# mcu.net
KiCad netlist of a schematic drawn in Altium Designer
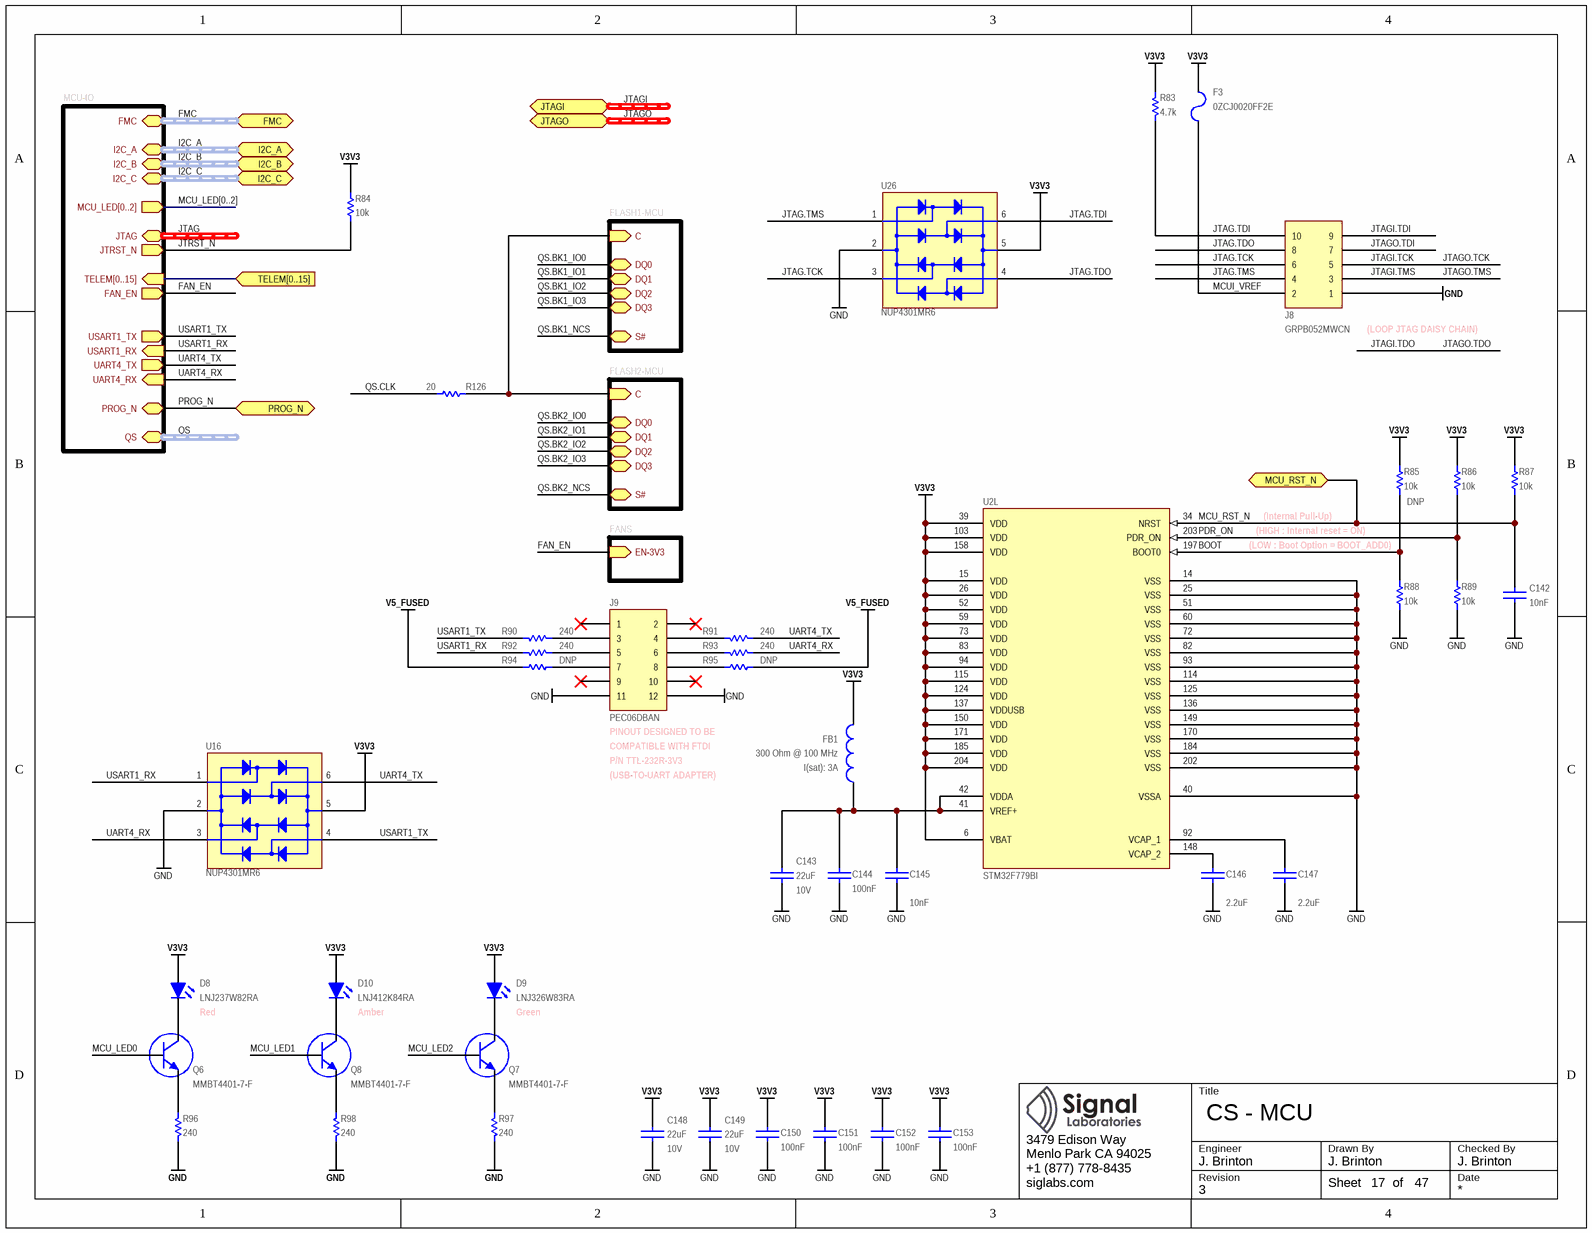
[diagram p0: mcu.SchDoc]

(export (version "E")
  (design (tool "Eeschema 10.0.6"))
  (components
    (comp (ref "C142")
      (value "10nF")
      (footprint "CAPC100X50X55L25N")
      (description "Ceramic Capacitor 10nF ±10% 50V X7R 0402")
      (fields (field (name "TOLERANCE") "±10%") (field (name "MANUFACTURER") "Murata"))
      (libsource (lib "generic") (part "Cap"))
    )
    (comp (ref "C143")
      (value "22uF")
      (footprint "CAPC200X125X145L45N")
      (description "Ceramic Capacitor 22uF ±20% 10V X7S 0805")
      (fields
        (field (name "MANUFACTURER") "TDK")
        (field (name "TOLERANCE") "±20%")
        (field (name "VOLTAGE") "10V")
      )
      (libsource (lib "") (part "CAP_1"))
    )
    (comp (ref "C144")
      (value "100nF")
      (footprint "CAPC100X50X55L25N")
      (description "Ceramic Capacitor 100nF ±10% 50V X7R 0402")
      (fields (field (name "VOLTAGE") "50V") (field (name "MANUFACTURER") "Murata"))
      (libsource (lib "generic") (part "CAP"))
    )
    (comp (ref "C145")
      (value "10nF")
      (footprint "CAPC100X50X55L25N")
      (description "Ceramic Capacitor 10nF ±10% 50V X7R 0402")
      (fields (field (name "TOLERANCE") "±10%") (field (name "MANUFACTURER") "Murata"))
      (libsource (lib "generic") (part "Cap"))
    )
    (comp (ref "C146")
      (value "2.2uF")
      (footprint "CAPC160X80X90L20N")
      (description "Ceramic Capacitor 2.2uF ±20% 10V X7R 0603")
      (fields (field (name "TOLERANCE") "±20%") (field (name "MANUFACTURER") "TDK"))
      (libsource (lib "generic") (part "Cap"))
    )
    (comp (ref "C147")
      (value "2.2uF")
      (footprint "CAPC160X80X90L20N")
      (description "Ceramic Capacitor 2.2uF ±20% 10V X7R 0603")
      (fields (field (name "TOLERANCE") "±20%") (field (name "MANUFACTURER") "TDK"))
      (libsource (lib "generic") (part "Cap"))
    )
    (comp (ref "C148")
      (value "22uF")
      (footprint "CAPC200X125X145L45N")
      (description "Ceramic Capacitor 22uF ±20% 10V X7S 0805")
      (fields
        (field (name "MANUFACTURER") "TDK")
        (field (name "TOLERANCE") "±20%")
        (field (name "VOLTAGE") "10V")
      )
      (libsource (lib "") (part "CAP_1"))
    )
    (comp (ref "C149")
      (value "22uF")
      (footprint "CAPC200X125X145L45N")
      (description "Ceramic Capacitor 22uF ±20% 10V X7S 0805")
      (fields
        (field (name "MANUFACTURER") "TDK")
        (field (name "TOLERANCE") "±20%")
        (field (name "VOLTAGE") "10V")
      )
      (libsource (lib "") (part "CAP_1"))
    )
    (comp (ref "C150")
      (value "100nF")
      (footprint "CAPC100X50X55L25N")
      (description "Ceramic Capacitor 100nF ±10% 50V X7R 0402")
      (fields (field (name "VOLTAGE") "50V") (field (name "MANUFACTURER") "Murata"))
      (libsource (lib "generic") (part "CAP"))
    )
    (comp (ref "C151")
      (value "100nF")
      (footprint "CAPC100X50X55L25N")
      (description "Ceramic Capacitor 100nF ±10% 50V X7R 0402")
      (fields (field (name "VOLTAGE") "50V") (field (name "MANUFACTURER") "Murata"))
      (libsource (lib "generic") (part "CAP"))
    )
    (comp (ref "C152")
      (value "100nF")
      (footprint "CAPC100X50X55L25N")
      (description "Ceramic Capacitor 100nF ±10% 50V X7R 0402")
      (fields (field (name "VOLTAGE") "50V") (field (name "MANUFACTURER") "Murata"))
      (libsource (lib "generic") (part "CAP"))
    )
    (comp (ref "C153")
      (value "100nF")
      (footprint "CAPC100X50X55L25N")
      (description "Ceramic Capacitor 100nF ±10% 50V X7R 0402")
      (fields (field (name "VOLTAGE") "50V") (field (name "MANUFACTURER") "Murata"))
      (libsource (lib "generic") (part "CAP"))
    )
    (comp (ref "D8")
      (value "LNJ237W82RA")
      (footprint "0603_LED")
      (description "LED, SMT 0603, Color Red, 5mA, 1.85V")
      (fields (field (name "MANUFACTURER") "Panasonic"))
      (libsource (lib "generic") (part "LED0603RD"))
    )
    (comp (ref "D9")
      (value "LNJ326W83RA")
      (footprint "0603_LED")
      (description "LED, SMT 0603, Color Green, 10mA, 2.05V")
      (fields (field (name "MANUFACTURER") "Panasonic"))
      (libsource (lib "generic") (part "LED0603GR"))
    )
    (comp (ref "D10")
      (value "LNJ412K84RA")
      (footprint "0603_LED")
      (description "LED, SMT 0603, Color Amber, 10mA, 2.05V")
      (fields (field (name "MANUFACTURER") "Panasonic"))
      (libsource (lib "generic") (part "LED0603Y"))
    )
    (comp (ref "F3")
      (value "0ZCJ0020FF2E")
      (footprint "generic:1206")
      (description "PTC Resettable Fuse, 0.2A, 30V, SMD 1206")
      (fields (field (name "MANUFACTURER") "Bell Fuse"))
      (libsource (lib "bel-fuse") (part "0ZCJ0020FF2E"))
    )
    (comp (ref "FB1")
      (value "300 Ohm @ 100 MHz")
      (footprint "0805")
      (description "Ferrite Chip 300 Ohm @ 100MHz; 3A")
      (fields
        (field (name "MANUFACTURER") "Wurth Electronics, Inc")
        (field (name "I(SAT)") "3A")
        (field (name "Comment") "742792031")
      )
      (libsource (lib "generic") (part "INDUCTOR"))
    )
    (comp (ref "J8")
      (value "GRPB052MWCN")
      (footprint "sullins:GRPB052MWCN")
      (description "Male Header, 0.050\" Pitch, 2x5 Position, Right Angle")
      (fields (field (name "MANUFACTURER") "Sullins"))
      (libsource (lib "sullins") (part "GRPB052VWVN"))
    )
    (comp (ref "J9")
      (value "PEC06DBAN")
      (footprint "HDR2X6H")
      (description "Header, 6-Pin, Dual row, Right Angle")
      (fields (field (name "MANUFACTURER") "Sullins"))
      (libsource (lib "Miscellaneous Connectors") (part "Header 6X2H"))
    )
    (comp (ref "Q6")
      (value "MMBT4401-7-F")
      (footprint "generic:SOT23")
      (description "NPN Small Signal Transistor SMD SOT-23")
      (fields (field (name "MANUFACTURER P/N") "MMBT4401-7-F") (field (name "MANUFACTURER") "Diodes, Inc."))
      (libsource (lib "diodes_inc") (part "MMBT4401-7-F"))
    )
    (comp (ref "Q7")
      (value "MMBT4401-7-F")
      (footprint "generic:SOT23")
      (description "NPN Small Signal Transistor SMD SOT-23")
      (fields (field (name "MANUFACTURER P/N") "MMBT4401-7-F") (field (name "MANUFACTURER") "Diodes, Inc."))
      (libsource (lib "diodes_inc") (part "MMBT4401-7-F"))
    )
    (comp (ref "Q8")
      (value "MMBT4401-7-F")
      (footprint "generic:SOT23")
      (description "NPN Small Signal Transistor SMD SOT-23")
      (fields (field (name "MANUFACTURER P/N") "MMBT4401-7-F") (field (name "MANUFACTURER") "Diodes, Inc."))
      (libsource (lib "diodes_inc") (part "MMBT4401-7-F"))
    )
    (comp (ref "R83")
      (value "4.7k")
      (footprint "RESC1005X40N")
      (description "Thick Film Resistor 4.7k ±1% 0.1W 75V 0402")
      (fields (field (name "TOLERANCE") "±1%") (field (name "MANUFACTURER") "Panasonic"))
      (libsource (lib "generic") (part "RES"))
    )
    (comp (ref "R84")
      (value "10k")
      (footprint "RESC1005X40N")
      (description "Thick Film Resistor 10k ±1% 0.1W 50V 0402")
      (fields (field (name "MANUFACTURER") "Panasonic") (field (name "TOLERANCE") "±1%"))
      (libsource (lib "generic") (part "RES"))
    )
    (comp (ref "R85")
      (value "10k")
      (footprint "RESC1005X40N")
      (description "Thick Film Resistor 10k ±1% 0.1W 50V 0402")
      (fields
        (field (name "MANUFACTURER") "Panasonic")
        (field (name "TOLERANCE") "±1%")
        (field (name "DO NOT PLACE") "DNP")
      )
      (libsource (lib "generic") (part "RES"))
    )
    (comp (ref "R86")
      (value "10k")
      (footprint "RESC1005X40N")
      (description "Thick Film Resistor 10k ±1% 0.1W 50V 0402")
      (fields (field (name "MANUFACTURER") "Panasonic") (field (name "TOLERANCE") "±1%"))
      (libsource (lib "generic") (part "RES"))
    )
    (comp (ref "R87")
      (value "10k")
      (footprint "RESC1005X40N")
      (description "Thick Film Resistor 10k ±1% 0.1W 50V 0402")
      (fields (field (name "MANUFACTURER") "Panasonic") (field (name "TOLERANCE") "±1%"))
      (libsource (lib "generic") (part "RES"))
    )
    (comp (ref "R88")
      (value "10k")
      (footprint "RESC1005X40N")
      (description "Thick Film Resistor 10k ±1% 0.1W 50V 0402")
      (fields (field (name "MANUFACTURER") "Panasonic") (field (name "TOLERANCE") "±1%"))
      (libsource (lib "generic") (part "RES"))
    )
    (comp (ref "R89")
      (value "10k")
      (footprint "RESC1005X40N")
      (description "Thick Film Resistor 10k ±1% 0.1W 50V 0402")
      (fields (field (name "MANUFACTURER") "Panasonic") (field (name "TOLERANCE") "±1%"))
      (libsource (lib "generic") (part "RES"))
    )
    (comp (ref "R90")
      (value "240")
      (footprint "RESC1005X40N")
      (description "Thick Film Resistor 240 ±1% 0.1W 75V 0402")
      (fields (field (name "TOLERANCE") "±1%") (field (name "MANUFACTURER") "Panasonic"))
      (libsource (lib "generic") (part "RES"))
    )
    (comp (ref "R91")
      (value "240")
      (footprint "RESC1005X40N")
      (description "Thick Film Resistor 240 ±1% 0.1W 75V 0402")
      (fields (field (name "TOLERANCE") "±1%") (field (name "MANUFACTURER") "Panasonic"))
      (libsource (lib "generic") (part "RES"))
    )
    (comp (ref "R92")
      (value "240")
      (footprint "RESC1005X40N")
      (description "Thick Film Resistor 240 ±1% 0.1W 75V 0402")
      (fields (field (name "TOLERANCE") "±1%") (field (name "MANUFACTURER") "Panasonic"))
      (libsource (lib "generic") (part "RES"))
    )
    (comp (ref "R93")
      (value "240")
      (footprint "RESC1005X40N")
      (description "Thick Film Resistor 240 ±1% 0.1W 75V 0402")
      (fields (field (name "TOLERANCE") "±1%") (field (name "MANUFACTURER") "Panasonic"))
      (libsource (lib "generic") (part "RES"))
    )
    (comp (ref "R94")
      (value "SOLDER_LINK")
      (footprint "SOLDERLINK0603X26N")
      (description "Solder Link")
      (fields (field (name "DO NOT PLACE") "DNP"))
      (libsource (lib "generic") (part "RES"))
    )
    (comp (ref "R95")
      (value "SOLDER_LINK")
      (footprint "SOLDERLINK0603X26N")
      (description "Solder Link")
      (fields (field (name "DO NOT PLACE") "DNP"))
      (libsource (lib "generic") (part "RES"))
    )
    (comp (ref "R96")
      (value "240")
      (footprint "RESC1005X40N")
      (description "Thick Film Resistor 240 ±1% 0.1W 75V 0402")
      (fields (field (name "TOLERANCE") "±1%") (field (name "MANUFACTURER") "Panasonic"))
      (libsource (lib "generic") (part "RES"))
    )
    (comp (ref "R97")
      (value "240")
      (footprint "RESC1005X40N")
      (description "Thick Film Resistor 240 ±1% 0.1W 75V 0402")
      (fields (field (name "TOLERANCE") "±1%") (field (name "MANUFACTURER") "Panasonic"))
      (libsource (lib "generic") (part "RES"))
    )
    (comp (ref "R98")
      (value "240")
      (footprint "RESC1005X40N")
      (description "Thick Film Resistor 240 ±1% 0.1W 75V 0402")
      (fields (field (name "TOLERANCE") "±1%") (field (name "MANUFACTURER") "Panasonic"))
      (libsource (lib "generic") (part "RES"))
    )
    (comp (ref "R126")
      (value "20")
      (footprint "RESC1005X40N")
      (description "Thick Film Resistor 20 ±1% 0.1W 75V 0402")
      (fields (field (name "TOLERANCE") "±1%") (field (name "MANUFACTURER") "Panasonic"))
      (libsource (lib "generic") (part "RES"))
    )
    (comp (ref "U2")
      (value "STM32F779BI")
      (footprint "LQFP208")
      (description "STM32 Microcontroller")
      (fields (field (name "MANUFACTURER") "ST Microelectronics"))
      (libsource (lib "hadley") (part "STM32F746BGT6"))
    )
    (comp (ref "U16")
      (value "NUP4301MR6")
      (footprint "generic:SOT23-6")
      (description "4-Lane TVS Diode Array")
      (fields (field (name "MANUFACTURER") "On Semiconductor"))
      (libsource (lib "on_semi") (part "NUP4301MR6"))
    )
    (comp (ref "U26")
      (value "NUP4301MR6")
      (footprint "generic:SOT23-6")
      (description "4-Lane TVS Diode Array")
      (fields (field (name "MANUFACTURER") "On Semiconductor"))
      (libsource (lib "on_semi") (part "NUP4301MR6"))
    )
  )
  (nets
    (net (code "25") (name "/BOOT") (class "Default")
      (node (ref "R85") (pin "1") (pinfunction "1_1") (pintype "passive"))
      (node (ref "R88") (pin "2") (pinfunction "2_2") (pintype "passive"))
      (node (ref "U2") (pin "197") (pinfunction "BOOT0_197") (pintype "input"))
    )
    (net (code "26") (name "/C") (class "Default")
      (node (ref "R126") (pin "2") (pinfunction "2_2") (pintype "passive"))
    )
    (net (code "28") (name "/JTAG.TCK") (class "Default")
      (node (ref "J8") (pin "6") (pinfunction "6_6") (pintype "passive"))
      (node (ref "U26") (pin "3") (pinfunction "B_3") (pintype "passive"))
    )
    (net (code "29") (name "/JTAG.TDI") (class "Default")
      (node (ref "J8") (pin "10") (pinfunction "10_10") (pintype "passive"))
      (node (ref "R83") (pin "1") (pinfunction "1_1") (pintype "passive"))
      (node (ref "U26") (pin "6") (pinfunction "D_6") (pintype "passive"))
    )
    (net (code "30") (name "/JTAG.TDO") (class "Default")
      (node (ref "J8") (pin "8") (pinfunction "8_8") (pintype "passive"))
      (node (ref "U26") (pin "4") (pinfunction "C_4") (pintype "passive"))
    )
    (net (code "31") (name "/JTAG.TMS") (class "Default")
      (node (ref "J8") (pin "4") (pinfunction "4_4") (pintype "passive"))
      (node (ref "U26") (pin "1") (pinfunction "A_1") (pintype "passive"))
    )
    (net (code "32") (name "/JTAGI.TCK") (class "Default")
      (node (ref "J8") (pin "5") (pinfunction "5_5") (pintype "passive"))
    )
    (net (code "33") (name "/JTAGI.TDI") (class "Default")
      (node (ref "J8") (pin "9") (pinfunction "9_9") (pintype "passive"))
    )
    (net (code "35") (name "/JTAGI.TMS") (class "Default")
      (node (ref "J8") (pin "3") (pinfunction "3_3") (pintype "passive"))
    )
    (net (code "36") (name "/JTAGO.TDI") (class "Default")
      (node (ref "J8") (pin "7") (pinfunction "7_7") (pintype "passive"))
    )
    (net (code "37") (name "/JTRST_N") (class "Default")
      (node (ref "R84") (pin "1") (pinfunction "1_1") (pintype "passive"))
    )
    (net (code "38") (name "/MCUI_VREF") (class "Default")
      (node (ref "F3") (pin "2") (pinfunction "2_2") (pintype "passive"))
      (node (ref "J8") (pin "2") (pinfunction "2_2") (pintype "passive"))
    )
    (net (code "39") (name "/MCU_LED0") (class "Default")
      (node (ref "Q6") (pin "1") (pinfunction "B_1") (pintype "passive"))
    )
    (net (code "40") (name "/MCU_LED1") (class "Default")
      (node (ref "Q8") (pin "1") (pinfunction "B_1") (pintype "passive"))
    )
    (net (code "41") (name "/MCU_LED2") (class "Default")
      (node (ref "Q7") (pin "1") (pinfunction "B_1") (pintype "passive"))
    )
    (net (code "43") (name "/MCU_RST_N") (class "Default")
      (node (ref "C142") (pin "2") (pinfunction "2_2") (pintype "passive"))
      (node (ref "R87") (pin "1") (pinfunction "1_1") (pintype "passive"))
      (node (ref "U2") (pin "34") (pinfunction "NRST_34") (pintype "input"))
    )
    (net (code "44") (name "/PDR_ON") (class "Default")
      (node (ref "R86") (pin "1") (pinfunction "1_1") (pintype "passive"))
      (node (ref "R89") (pin "2") (pinfunction "2_2") (pintype "passive"))
      (node (ref "U2") (pin "203") (pinfunction "PDR_ON_203") (pintype "input"))
    )
    (net (code "56") (name "/QS.CLK") (class "Default")
      (node (ref "R126") (pin "1") (pinfunction "1_1") (pintype "passive"))
    )
    (net (code "58") (name "/UART4_RX") (class "Default")
      (node (ref "R93") (pin "2") (pinfunction "2_2") (pintype "passive"))
      (node (ref "U16") (pin "3") (pinfunction "B_3") (pintype "passive"))
    )
    (net (code "59") (name "/UART4_TX") (class "Default")
      (node (ref "R91") (pin "2") (pinfunction "2_2") (pintype "passive"))
      (node (ref "U16") (pin "6") (pinfunction "D_6") (pintype "passive"))
    )
    (net (code "60") (name "/USART1_RX") (class "Default")
      (node (ref "R92") (pin "1") (pinfunction "1_1") (pintype "passive"))
      (node (ref "U16") (pin "1") (pinfunction "A_1") (pintype "passive"))
    )
    (net (code "61") (name "/USART1_TX") (class "Default")
      (node (ref "R90") (pin "1") (pinfunction "1_1") (pintype "passive"))
      (node (ref "U16") (pin "4") (pinfunction "C_4") (pintype "passive"))
    )
    (net (code "70") (name "GND") (class "Default")
      (node (ref "C142") (pin "1") (pinfunction "1_1") (pintype "passive"))
      (node (ref "C143") (pin "2") (pinfunction "2_2") (pintype "passive"))
      (node (ref "C144") (pin "1") (pinfunction "1_1") (pintype "passive"))
      (node (ref "C145") (pin "1") (pinfunction "1_1") (pintype "passive"))
      (node (ref "C146") (pin "1") (pinfunction "1_1") (pintype "passive"))
      (node (ref "C147") (pin "1") (pinfunction "1_1") (pintype "passive"))
      (node (ref "C148") (pin "2") (pinfunction "2_2") (pintype "passive"))
      (node (ref "C149") (pin "2") (pinfunction "2_2") (pintype "passive"))
      (node (ref "C150") (pin "1") (pinfunction "1_1") (pintype "passive"))
      (node (ref "C151") (pin "1") (pinfunction "1_1") (pintype "passive"))
      (node (ref "C152") (pin "1") (pinfunction "1_1") (pintype "passive"))
      (node (ref "C153") (pin "1") (pinfunction "1_1") (pintype "passive"))
      (node (ref "J8") (pin "1") (pinfunction "1_1") (pintype "passive"))
      (node (ref "J9") (pin "11") (pinfunction "11_11") (pintype "passive"))
      (node (ref "J9") (pin "12") (pinfunction "12_12") (pintype "passive"))
      (node (ref "R88") (pin "1") (pinfunction "1_1") (pintype "passive"))
      (node (ref "R89") (pin "1") (pinfunction "1_1") (pintype "passive"))
      (node (ref "R96") (pin "2") (pinfunction "2_2") (pintype "passive"))
      (node (ref "R97") (pin "2") (pinfunction "2_2") (pintype "passive"))
      (node (ref "R98") (pin "2") (pinfunction "2_2") (pintype "passive"))
      (node (ref "U16") (pin "2") (pinfunction "VN_2") (pintype "passive"))
      (node (ref "U2") (pin "114") (pinfunction "VSS_114") (pintype "power_in"))
      (node (ref "U2") (pin "125") (pinfunction "VSS_125") (pintype "power_in"))
      (node (ref "U2") (pin "136") (pinfunction "VSS_136") (pintype "power_in"))
      (node (ref "U2") (pin "14") (pinfunction "VSS_14") (pintype "power_in"))
      (node (ref "U2") (pin "149") (pinfunction "VSS_149") (pintype "power_in"))
      (node (ref "U2") (pin "170") (pinfunction "VSS_170") (pintype "power_in"))
      (node (ref "U2") (pin "184") (pinfunction "VSS_184") (pintype "power_in"))
      (node (ref "U2") (pin "202") (pinfunction "VSS_202") (pintype "power_in"))
      (node (ref "U2") (pin "25") (pinfunction "VSS_25") (pintype "power_in"))
      (node (ref "U2") (pin "40") (pinfunction "VSSA_40") (pintype "power_in"))
      (node (ref "U2") (pin "51") (pinfunction "VSS_51") (pintype "power_in"))
      (node (ref "U2") (pin "60") (pinfunction "VSS_60") (pintype "power_in"))
      (node (ref "U2") (pin "72") (pinfunction "VSS_72") (pintype "power_in"))
      (node (ref "U2") (pin "82") (pinfunction "VSS_82") (pintype "power_in"))
      (node (ref "U2") (pin "93") (pinfunction "VSS_93") (pintype "power_in"))
      (node (ref "U26") (pin "2") (pinfunction "VN_2") (pintype "passive"))
    )
    (net (code "71") (name "Net-(D8-K)") (class "Default")
      (node (ref "D8") (pin "2") (pinfunction "K_2") (pintype "passive"))
      (node (ref "Q6") (pin "3") (pinfunction "C_3") (pintype "passive"))
    )
    (net (code "72") (name "Net-(D9-K)") (class "Default")
      (node (ref "D9") (pin "2") (pinfunction "K_2") (pintype "passive"))
      (node (ref "Q7") (pin "3") (pinfunction "C_3") (pintype "passive"))
    )
    (net (code "73") (name "Net-(D10-K)") (class "Default")
      (node (ref "D10") (pin "2") (pinfunction "K_2") (pintype "passive"))
      (node (ref "Q8") (pin "3") (pinfunction "C_3") (pintype "passive"))
    )
    (net (code "74") (name "Net-(J9-Pad3)") (class "Default")
      (node (ref "J9") (pin "3") (pinfunction "3_3") (pintype "passive"))
      (node (ref "R90") (pin "2") (pinfunction "2_2") (pintype "passive"))
    )
    (net (code "75") (name "Net-(J9-Pad4)") (class "Default")
      (node (ref "J9") (pin "4") (pinfunction "4_4") (pintype "passive"))
      (node (ref "R91") (pin "1") (pinfunction "1_1") (pintype "passive"))
    )
    (net (code "76") (name "Net-(J9-Pad5)") (class "Default")
      (node (ref "J9") (pin "5") (pinfunction "5_5") (pintype "passive"))
      (node (ref "R92") (pin "2") (pinfunction "2_2") (pintype "passive"))
    )
    (net (code "77") (name "Net-(J9-Pad6)") (class "Default")
      (node (ref "J9") (pin "6") (pinfunction "6_6") (pintype "passive"))
      (node (ref "R93") (pin "1") (pinfunction "1_1") (pintype "passive"))
    )
    (net (code "78") (name "Net-(J9-Pad7)") (class "Default")
      (node (ref "J9") (pin "7") (pinfunction "7_7") (pintype "passive"))
      (node (ref "R94") (pin "1") (pinfunction "1_1") (pintype "passive"))
    )
    (net (code "79") (name "Net-(J9-Pad8)") (class "Default")
      (node (ref "J9") (pin "8") (pinfunction "8_8") (pintype "passive"))
      (node (ref "R95") (pin "2") (pinfunction "2_2") (pintype "passive"))
    )
    (net (code "80") (name "Net-(Q6-E)") (class "Default")
      (node (ref "Q6") (pin "2") (pinfunction "E_2") (pintype "passive"))
      (node (ref "R96") (pin "1") (pinfunction "1_1") (pintype "passive"))
    )
    (net (code "81") (name "Net-(Q7-E)") (class "Default")
      (node (ref "Q7") (pin "2") (pinfunction "E_2") (pintype "passive"))
      (node (ref "R97") (pin "1") (pinfunction "1_1") (pintype "passive"))
    )
    (net (code "82") (name "Net-(Q8-E)") (class "Default")
      (node (ref "Q8") (pin "2") (pinfunction "E_2") (pintype "passive"))
      (node (ref "R98") (pin "1") (pinfunction "1_1") (pintype "passive"))
    )
    (net (code "83") (name "Net-(U2L-VCAP_1)") (class "Default")
      (node (ref "C147") (pin "2") (pinfunction "2_2") (pintype "passive"))
      (node (ref "U2") (pin "92") (pinfunction "VCAP_1_92") (pintype "power_in"))
    )
    (net (code "84") (name "Net-(U2L-VCAP_2)") (class "Default")
      (node (ref "C146") (pin "2") (pinfunction "2_2") (pintype "passive"))
      (node (ref "U2") (pin "148") (pinfunction "VCAP_2_148") (pintype "power_in"))
    )
    (net (code "85") (name "Net-(U2L-VDDA)") (class "Default")
      (node (ref "C143") (pin "1") (pinfunction "1_1") (pintype "passive"))
      (node (ref "C144") (pin "2") (pinfunction "2_2") (pintype "passive"))
      (node (ref "C145") (pin "2") (pinfunction "2_2") (pintype "passive"))
      (node (ref "FB1") (pin "1") (pinfunction "1_1") (pintype "passive"))
      (node (ref "U2") (pin "41") (pinfunction "VREF+_41") (pintype "power_in"))
      (node (ref "U2") (pin "42") (pinfunction "VDDA_42") (pintype "power_in"))
    )
    (net (code "86") (name "V3V3") (class "Default")
      (node (ref "C148") (pin "1") (pinfunction "1_1") (pintype "passive"))
      (node (ref "C149") (pin "1") (pinfunction "1_1") (pintype "passive"))
      (node (ref "C150") (pin "2") (pinfunction "2_2") (pintype "passive"))
      (node (ref "C151") (pin "2") (pinfunction "2_2") (pintype "passive"))
      (node (ref "C152") (pin "2") (pinfunction "2_2") (pintype "passive"))
      (node (ref "C153") (pin "2") (pinfunction "2_2") (pintype "passive"))
      (node (ref "D10") (pin "1") (pinfunction "A_1") (pintype "passive"))
      (node (ref "D8") (pin "1") (pinfunction "A_1") (pintype "passive"))
      (node (ref "D9") (pin "1") (pinfunction "A_1") (pintype "passive"))
      (node (ref "F3") (pin "1") (pinfunction "1_1") (pintype "passive"))
      (node (ref "FB1") (pin "2") (pinfunction "2_2") (pintype "passive"))
      (node (ref "R83") (pin "2") (pinfunction "2_2") (pintype "passive"))
      (node (ref "R84") (pin "2") (pinfunction "2_2") (pintype "passive"))
      (node (ref "R85") (pin "2") (pinfunction "2_2") (pintype "passive"))
      (node (ref "R86") (pin "2") (pinfunction "2_2") (pintype "passive"))
      (node (ref "R87") (pin "2") (pinfunction "2_2") (pintype "passive"))
      (node (ref "U16") (pin "5") (pinfunction "VP_5") (pintype "passive"))
      (node (ref "U2") (pin "103") (pinfunction "VDD_103") (pintype "power_in"))
      (node (ref "U2") (pin "115") (pinfunction "VDD_115") (pintype "power_in"))
      (node (ref "U2") (pin "124") (pinfunction "VDD_124") (pintype "power_in"))
      (node (ref "U2") (pin "137") (pinfunction "VDDUSB_137") (pintype "power_in"))
      (node (ref "U2") (pin "15") (pinfunction "VDD_15") (pintype "power_in"))
      (node (ref "U2") (pin "150") (pinfunction "VDD_150") (pintype "power_in"))
      (node (ref "U2") (pin "158") (pinfunction "VDD_158") (pintype "power_in"))
      (node (ref "U2") (pin "171") (pinfunction "VDD_171") (pintype "power_in"))
      (node (ref "U2") (pin "185") (pinfunction "VDD_185") (pintype "power_in"))
      (node (ref "U2") (pin "204") (pinfunction "VDD_204") (pintype "power_in"))
      (node (ref "U2") (pin "26") (pinfunction "VDD_26") (pintype "power_in"))
      (node (ref "U2") (pin "39") (pinfunction "VDD_39") (pintype "power_in"))
      (node (ref "U2") (pin "52") (pinfunction "VDD_52") (pintype "power_in"))
      (node (ref "U2") (pin "59") (pinfunction "VDD_59") (pintype "power_in"))
      (node (ref "U2") (pin "6") (pinfunction "VBAT_6") (pintype "power_in"))
      (node (ref "U2") (pin "73") (pinfunction "VDD_73") (pintype "power_in"))
      (node (ref "U2") (pin "83") (pinfunction "VDD_83") (pintype "power_in"))
      (node (ref "U2") (pin "94") (pinfunction "VDD_94") (pintype "power_in"))
      (node (ref "U26") (pin "5") (pinfunction "VP_5") (pintype "passive"))
    )
    (net (code "87") (name "V5_FUSED") (class "Default")
      (node (ref "R94") (pin "2") (pinfunction "2_2") (pintype "passive"))
      (node (ref "R95") (pin "1") (pinfunction "1_1") (pintype "passive"))
    )
    (net (code "88") (name "unconnected-(J9-Pad1)") (class "Default")
      (node (ref "J9") (pin "1") (pinfunction "1_1") (pintype "passive+no_connect"))
    )
    (net (code "89") (name "unconnected-(J9-Pad2)") (class "Default")
      (node (ref "J9") (pin "2") (pinfunction "2_2") (pintype "passive+no_connect"))
    )
    (net (code "90") (name "unconnected-(J9-Pad9)") (class "Default")
      (node (ref "J9") (pin "9") (pinfunction "9_9") (pintype "passive+no_connect"))
    )
    (net (code "91") (name "unconnected-(J9-Pad10)") (class "Default")
      (node (ref "J9") (pin "10") (pinfunction "10_10") (pintype "passive+no_connect"))
    )
  )
)
